# T61.net
KiCad netlist of a schematic drawn in EAGLE
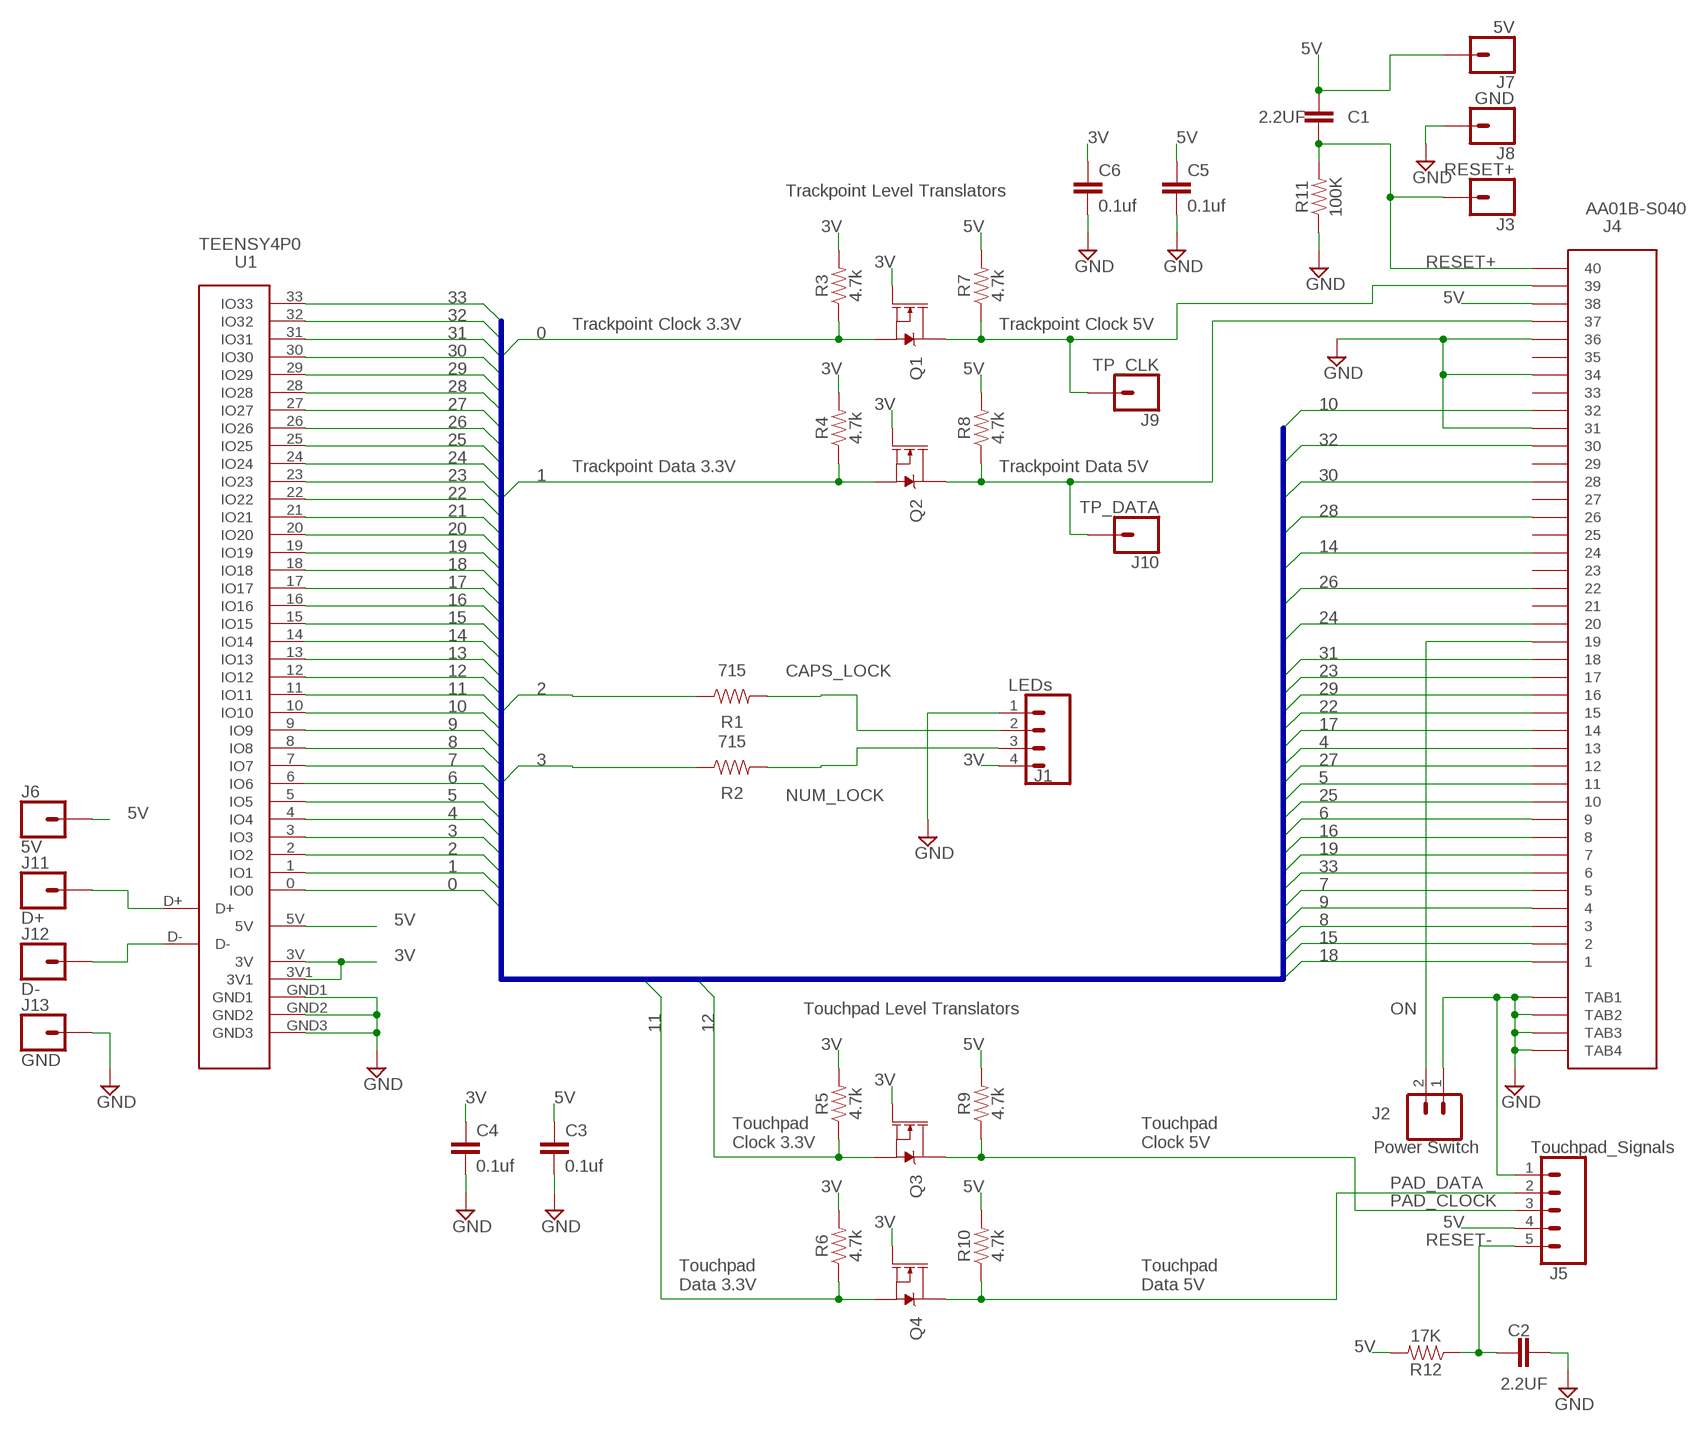
[diagram p0: schematic, sheet 1]

(export (version "E")
  (design (tool "Eeschema 10.0.6"))
  (components
    (comp (ref "C1")
      (value "2.2UF")
      (footprint "eagle-import:0603_CAP")
      (libsource (lib "eagle-import") (part "0603_CAP"))
    )
    (comp (ref "C2")
      (value "2.2UF")
      (footprint "eagle-import:0603_CAP")
      (libsource (lib "eagle-import") (part "0603_CAP"))
    )
    (comp (ref "C3")
      (value "0.1uf")
      (footprint "eagle-import:0603_CAP")
      (libsource (lib "eagle-import") (part "0603_CAP"))
    )
    (comp (ref "C4")
      (value "0.1uf")
      (footprint "eagle-import:0603_CAP")
      (libsource (lib "eagle-import") (part "0603_CAP"))
    )
    (comp (ref "C5")
      (value "0.1uf")
      (footprint "eagle-import:0603_CAP")
      (libsource (lib "eagle-import") (part "0603_CAP"))
    )
    (comp (ref "C6")
      (value "0.1uf")
      (footprint "eagle-import:0603_CAP")
      (libsource (lib "eagle-import") (part "0603_CAP"))
    )
    (comp (ref "J1")
      (value "LEDs")
      (footprint "eagle-import:1X04")
      (libsource (lib "eagle-import") (part "CONN_04"))
    )
    (comp (ref "J2")
      (value "Power Switch")
      (footprint "eagle-import:1X02")
      (libsource (lib "eagle-import") (part "CONN_02"))
    )
    (comp (ref "J3")
      (value "RESET+")
      (footprint "eagle-import:1X01_NO_SILK")
      (libsource (lib "eagle-import") (part "CONN_01PTH_NO_SILK_YES_STOP"))
    )
    (comp (ref "J4")
      (value "AA01B-S040")
      (footprint "eagle-import:WM6787_AA01B")
      (libsource (lib "eagle-import") (part "WM6787_A01B"))
    )
    (comp (ref "J5")
      (value "Touchpad_Signals")
      (footprint "eagle-import:1X05")
      (libsource (lib "eagle-import") (part "CONN_05"))
    )
    (comp (ref "J6")
      (value "5V")
      (footprint "eagle-import:1X01_NO_SILK")
      (libsource (lib "eagle-import") (part "CONN_01PTH_NO_SILK_YES_STOP"))
    )
    (comp (ref "J7")
      (value "5V")
      (footprint "eagle-import:1X01_NO_SILK")
      (libsource (lib "eagle-import") (part "CONN_01PTH_NO_SILK_YES_STOP"))
    )
    (comp (ref "J8")
      (value "GND")
      (footprint "eagle-import:1X01_NO_SILK")
      (libsource (lib "eagle-import") (part "CONN_01PTH_NO_SILK_YES_STOP"))
    )
    (comp (ref "J9")
      (value "TP_CLK")
      (footprint "eagle-import:1X01_NO_SILK")
      (libsource (lib "eagle-import") (part "CONN_01PTH_NO_SILK_YES_STOP"))
    )
    (comp (ref "J10")
      (value "TP_DATA")
      (footprint "eagle-import:1X01_NO_SILK")
      (libsource (lib "eagle-import") (part "CONN_01PTH_NO_SILK_YES_STOP"))
    )
    (comp (ref "J11")
      (value "D+")
      (footprint "eagle-import:1X01_NO_SILK")
      (libsource (lib "eagle-import") (part "CONN_01PTH_NO_SILK_YES_STOP"))
    )
    (comp (ref "J12")
      (value "D-")
      (footprint "eagle-import:1X01_NO_SILK")
      (libsource (lib "eagle-import") (part "CONN_01PTH_NO_SILK_YES_STOP"))
    )
    (comp (ref "J13")
      (value "GND")
      (footprint "eagle-import:1X01_NO_SILK")
      (libsource (lib "eagle-import") (part "CONN_01PTH_NO_SILK_YES_STOP"))
    )
    (comp (ref "Q1")
      (value "220mA/50V/3.5Ω")
      (footprint "eagle-import:SOT23-3")
      (libsource (lib "eagle-import") (part "MOSFET-NCH-BSS138"))
    )
    (comp (ref "Q2")
      (value "220mA/50V/3.5Ω")
      (footprint "eagle-import:SOT23-3")
      (libsource (lib "eagle-import") (part "MOSFET-NCH-BSS138"))
    )
    (comp (ref "Q3")
      (value "220mA/50V/3.5Ω")
      (footprint "eagle-import:SOT23-3")
      (libsource (lib "eagle-import") (part "MOSFET-NCH-BSS138"))
    )
    (comp (ref "Q4")
      (value "220mA/50V/3.5Ω")
      (footprint "eagle-import:SOT23-3")
      (libsource (lib "eagle-import") (part "MOSFET-NCH-BSS138"))
    )
    (comp (ref "R1")
      (value "715")
      (footprint "eagle-import:0603")
      (libsource (lib "eagle-import") (part "715OHM-0603-1/10W-1%"))
    )
    (comp (ref "R2")
      (value "715")
      (footprint "eagle-import:0603")
      (libsource (lib "eagle-import") (part "715OHM-0603-1/10W-1%"))
    )
    (comp (ref "R3")
      (value "4.7k")
      (footprint "eagle-import:0603")
      (libsource (lib "eagle-import") (part "4.7KOHM-0603-1/10W-1%"))
    )
    (comp (ref "R4")
      (value "4.7k")
      (footprint "eagle-import:0603")
      (libsource (lib "eagle-import") (part "4.7KOHM-0603-1/10W-1%"))
    )
    (comp (ref "R5")
      (value "4.7k")
      (footprint "eagle-import:0603")
      (libsource (lib "eagle-import") (part "4.7KOHM-0603-1/10W-1%"))
    )
    (comp (ref "R6")
      (value "4.7k")
      (footprint "eagle-import:0603")
      (libsource (lib "eagle-import") (part "4.7KOHM-0603-1/10W-1%"))
    )
    (comp (ref "R7")
      (value "4.7k")
      (footprint "eagle-import:0603")
      (libsource (lib "eagle-import") (part "4.7KOHM-0603-1/10W-1%"))
    )
    (comp (ref "R8")
      (value "4.7k")
      (footprint "eagle-import:0603")
      (libsource (lib "eagle-import") (part "4.7KOHM-0603-1/10W-1%"))
    )
    (comp (ref "R9")
      (value "4.7k")
      (footprint "eagle-import:0603")
      (libsource (lib "eagle-import") (part "4.7KOHM-0603-1/10W-1%"))
    )
    (comp (ref "R10")
      (value "4.7k")
      (footprint "eagle-import:0603")
      (libsource (lib "eagle-import") (part "4.7KOHM-0603-1/10W-1%"))
    )
    (comp (ref "R11")
      (value "100K")
      (footprint "eagle-import:0603_RESISTOR")
      (libsource (lib "eagle-import") (part "0603_RESISTOR"))
    )
    (comp (ref "R12")
      (value "17K")
      (footprint "eagle-import:0603_RESISTOR")
      (libsource (lib "eagle-import") (part "0603_RESISTOR"))
    )
    (comp (ref "U1")
      (value "TEENSY4P0")
      (footprint "eagle-import:TEENSY4P0")
      (libsource (lib "eagle-import") (part "TEENSY4P0"))
    )
  )
  (nets
    (net (code "1") (name "/0") (class "Default")
      (node (ref "Q1") (pin "2") (pinfunction "S_2") (pintype "bidirectional"))
      (node (ref "R3") (pin "1") (pinfunction "1_1") (pintype "passive"))
      (node (ref "U1") (pin "0") (pinfunction "IO0_0") (pintype "bidirectional"))
    )
    (net (code "2") (name "/1") (class "Default")
      (node (ref "Q2") (pin "2") (pinfunction "S_2") (pintype "bidirectional"))
      (node (ref "R4") (pin "1") (pinfunction "1_1") (pintype "passive"))
      (node (ref "U1") (pin "1") (pinfunction "IO1_1") (pintype "bidirectional"))
    )
    (net (code "3") (name "/2") (class "Default")
      (node (ref "R1") (pin "1") (pinfunction "1_1") (pintype "passive"))
      (node (ref "U1") (pin "2") (pinfunction "IO2_2") (pintype "bidirectional"))
    )
    (net (code "4") (name "/3") (class "Default")
      (node (ref "R2") (pin "1") (pinfunction "1_1") (pintype "passive"))
      (node (ref "U1") (pin "3") (pinfunction "IO3_3") (pintype "bidirectional"))
    )
    (net (code "5") (name "/3V") (class "Default")
      (node (ref "C4") (pin "1") (pinfunction "1_1") (pintype "passive"))
      (node (ref "C6") (pin "1") (pinfunction "1_1") (pintype "passive"))
      (node (ref "J1") (pin "4") (pinfunction "4_4") (pintype "passive"))
      (node (ref "Q1") (pin "1") (pinfunction "G_1") (pintype "bidirectional"))
      (node (ref "Q2") (pin "1") (pinfunction "G_1") (pintype "bidirectional"))
      (node (ref "Q3") (pin "1") (pinfunction "G_1") (pintype "bidirectional"))
      (node (ref "Q4") (pin "1") (pinfunction "G_1") (pintype "bidirectional"))
      (node (ref "R3") (pin "2") (pinfunction "2_2") (pintype "passive"))
      (node (ref "R4") (pin "2") (pinfunction "2_2") (pintype "passive"))
      (node (ref "R5") (pin "2") (pinfunction "2_2") (pintype "passive"))
      (node (ref "R6") (pin "2") (pinfunction "2_2") (pintype "passive"))
      (node (ref "U1") (pin "3V") (pinfunction "3V_3V") (pintype "bidirectional"))
      (node (ref "U1") (pin "3V1") (pinfunction "3V1_3V1") (pintype "bidirectional"))
    )
    (net (code "6") (name "/4") (class "Default")
      (node (ref "J4") (pin "P$13") (pinfunction "13_P$13") (pintype "bidirectional"))
      (node (ref "U1") (pin "4") (pinfunction "IO4_4") (pintype "bidirectional"))
    )
    (net (code "7") (name "/5") (class "Default")
      (node (ref "J4") (pin "P$11") (pinfunction "11_P$11") (pintype "bidirectional"))
      (node (ref "U1") (pin "5") (pinfunction "IO5_5") (pintype "bidirectional"))
    )
    (net (code "8") (name "/5V") (class "Default")
      (node (ref "C1") (pin "1") (pinfunction "1_1") (pintype "passive"))
      (node (ref "C3") (pin "1") (pinfunction "1_1") (pintype "passive"))
      (node (ref "C5") (pin "1") (pinfunction "1_1") (pintype "passive"))
      (node (ref "J4") (pin "P$38") (pinfunction "38_P$38") (pintype "bidirectional"))
      (node (ref "J5") (pin "4") (pinfunction "4_4") (pintype "passive"))
      (node (ref "J6") (pin "1") (pinfunction "1_1") (pintype "passive"))
      (node (ref "J7") (pin "1") (pinfunction "1_1") (pintype "passive"))
      (node (ref "R10") (pin "2") (pinfunction "2_2") (pintype "passive"))
      (node (ref "R12") (pin "2") (pinfunction "2_2") (pintype "passive"))
      (node (ref "R7") (pin "2") (pinfunction "2_2") (pintype "passive"))
      (node (ref "R8") (pin "2") (pinfunction "2_2") (pintype "passive"))
      (node (ref "R9") (pin "2") (pinfunction "2_2") (pintype "passive"))
      (node (ref "U1") (pin "5V") (pinfunction "5V_5V") (pintype "bidirectional"))
    )
    (net (code "9") (name "/6") (class "Default")
      (node (ref "J4") (pin "P$9") (pinfunction "9_P$9") (pintype "bidirectional"))
      (node (ref "U1") (pin "6") (pinfunction "IO6_6") (pintype "bidirectional"))
    )
    (net (code "10") (name "/7") (class "Default")
      (node (ref "J4") (pin "P$5") (pinfunction "5_P$5") (pintype "bidirectional"))
      (node (ref "U1") (pin "7") (pinfunction "IO7_7") (pintype "bidirectional"))
    )
    (net (code "11") (name "/8") (class "Default")
      (node (ref "J4") (pin "P$3") (pinfunction "3_P$3") (pintype "bidirectional"))
      (node (ref "U1") (pin "8") (pinfunction "IO8_8") (pintype "bidirectional"))
    )
    (net (code "12") (name "/9") (class "Default")
      (node (ref "J4") (pin "P$4") (pinfunction "4_P$4") (pintype "bidirectional"))
      (node (ref "U1") (pin "9") (pinfunction "IO9_9") (pintype "bidirectional"))
    )
    (net (code "13") (name "/10") (class "Default")
      (node (ref "J4") (pin "P$32") (pinfunction "32_P$32") (pintype "bidirectional"))
      (node (ref "U1") (pin "10") (pinfunction "IO10_10") (pintype "bidirectional"))
    )
    (net (code "14") (name "/11") (class "Default")
      (node (ref "Q4") (pin "2") (pinfunction "S_2") (pintype "bidirectional"))
      (node (ref "R6") (pin "1") (pinfunction "1_1") (pintype "passive"))
      (node (ref "U1") (pin "11") (pinfunction "IO11_11") (pintype "bidirectional"))
    )
    (net (code "15") (name "/12") (class "Default")
      (node (ref "Q3") (pin "2") (pinfunction "S_2") (pintype "bidirectional"))
      (node (ref "R5") (pin "1") (pinfunction "1_1") (pintype "passive"))
      (node (ref "U1") (pin "12") (pinfunction "IO12_12") (pintype "bidirectional"))
    )
    (net (code "16") (name "/13") (class "Default")
      (node (ref "U1") (pin "13") (pinfunction "IO13_13") (pintype "bidirectional"))
    )
    (net (code "17") (name "/14") (class "Default")
      (node (ref "J4") (pin "P$24") (pinfunction "24_P$24") (pintype "bidirectional"))
      (node (ref "U1") (pin "14") (pinfunction "IO14_14") (pintype "bidirectional"))
    )
    (net (code "18") (name "/15") (class "Default")
      (node (ref "J4") (pin "P$2") (pinfunction "2_P$2") (pintype "bidirectional"))
      (node (ref "U1") (pin "15") (pinfunction "IO15_15") (pintype "bidirectional"))
    )
    (net (code "19") (name "/16") (class "Default")
      (node (ref "J4") (pin "P$8") (pinfunction "8_P$8") (pintype "bidirectional"))
      (node (ref "U1") (pin "16") (pinfunction "IO16_16") (pintype "bidirectional"))
    )
    (net (code "20") (name "/17") (class "Default")
      (node (ref "J4") (pin "P$14") (pinfunction "14_P$14") (pintype "bidirectional"))
      (node (ref "U1") (pin "17") (pinfunction "IO17_17") (pintype "bidirectional"))
    )
    (net (code "21") (name "/18") (class "Default")
      (node (ref "J4") (pin "P$1") (pinfunction "1_P$1") (pintype "bidirectional"))
      (node (ref "U1") (pin "18") (pinfunction "IO18_18") (pintype "bidirectional"))
    )
    (net (code "22") (name "/19") (class "Default")
      (node (ref "J4") (pin "P$7") (pinfunction "7_P$7") (pintype "bidirectional"))
      (node (ref "U1") (pin "19") (pinfunction "IO19_19") (pintype "bidirectional"))
    )
    (net (code "23") (name "/20") (class "Default")
      (node (ref "U1") (pin "20") (pinfunction "IO20_20") (pintype "bidirectional"))
    )
    (net (code "24") (name "/21") (class "Default")
      (node (ref "U1") (pin "21") (pinfunction "IO21_21") (pintype "bidirectional"))
    )
    (net (code "25") (name "/22") (class "Default")
      (node (ref "J4") (pin "P$15") (pinfunction "15_P$15") (pintype "bidirectional"))
      (node (ref "U1") (pin "22") (pinfunction "IO22_22") (pintype "bidirectional"))
    )
    (net (code "26") (name "/23") (class "Default")
      (node (ref "J4") (pin "P$17") (pinfunction "17_P$17") (pintype "bidirectional"))
      (node (ref "U1") (pin "23") (pinfunction "IO23_23") (pintype "bidirectional"))
    )
    (net (code "27") (name "/24") (class "Default")
      (node (ref "J4") (pin "P$20") (pinfunction "20_P$20") (pintype "bidirectional"))
      (node (ref "U1") (pin "24") (pinfunction "IO24_24") (pintype "bidirectional"))
    )
    (net (code "28") (name "/25") (class "Default")
      (node (ref "J4") (pin "P$10") (pinfunction "10_P$10") (pintype "bidirectional"))
      (node (ref "U1") (pin "25") (pinfunction "IO25_25") (pintype "bidirectional"))
    )
    (net (code "29") (name "/26") (class "Default")
      (node (ref "J4") (pin "P$22") (pinfunction "22_P$22") (pintype "bidirectional"))
      (node (ref "U1") (pin "26") (pinfunction "IO26_26") (pintype "bidirectional"))
    )
    (net (code "30") (name "/27") (class "Default")
      (node (ref "J4") (pin "P$12") (pinfunction "12_P$12") (pintype "bidirectional"))
      (node (ref "U1") (pin "27") (pinfunction "IO27_27") (pintype "bidirectional"))
    )
    (net (code "31") (name "/28") (class "Default")
      (node (ref "J4") (pin "P$26") (pinfunction "26_P$26") (pintype "bidirectional"))
      (node (ref "U1") (pin "28") (pinfunction "IO28_28") (pintype "bidirectional"))
    )
    (net (code "32") (name "/29") (class "Default")
      (node (ref "J4") (pin "P$16") (pinfunction "16_P$16") (pintype "bidirectional"))
      (node (ref "U1") (pin "29") (pinfunction "IO29_29") (pintype "bidirectional"))
    )
    (net (code "33") (name "/30") (class "Default")
      (node (ref "J4") (pin "P$28") (pinfunction "28_P$28") (pintype "bidirectional"))
      (node (ref "U1") (pin "30") (pinfunction "IO30_30") (pintype "bidirectional"))
    )
    (net (code "34") (name "/31") (class "Default")
      (node (ref "J4") (pin "P$18") (pinfunction "18_P$18") (pintype "bidirectional"))
      (node (ref "U1") (pin "31") (pinfunction "IO31_31") (pintype "bidirectional"))
    )
    (net (code "35") (name "/32") (class "Default")
      (node (ref "J4") (pin "P$30") (pinfunction "30_P$30") (pintype "bidirectional"))
      (node (ref "U1") (pin "32") (pinfunction "IO32_32") (pintype "bidirectional"))
    )
    (net (code "36") (name "/33") (class "Default")
      (node (ref "J4") (pin "P$6") (pinfunction "6_P$6") (pintype "bidirectional"))
      (node (ref "U1") (pin "33") (pinfunction "IO33_33") (pintype "bidirectional"))
    )
    (net (code "37") (name "/CAPS_LOCK") (class "Default")
      (node (ref "J1") (pin "2") (pinfunction "2_2") (pintype "passive"))
      (node (ref "R1") (pin "2") (pinfunction "2_2") (pintype "passive"))
    )
    (net (code "38") (name "/NUM_LOCK") (class "Default")
      (node (ref "J1") (pin "3") (pinfunction "3_3") (pintype "passive"))
      (node (ref "R2") (pin "2") (pinfunction "2_2") (pintype "passive"))
    )
    (net (code "39") (name "/ON") (class "Default")
      (node (ref "J2") (pin "2") (pinfunction "2_2") (pintype "passive"))
      (node (ref "J4") (pin "P$19") (pinfunction "19_P$19") (pintype "bidirectional"))
    )
    (net (code "40") (name "/PAD_CLOCK") (class "Default")
      (node (ref "J5") (pin "3") (pinfunction "3_3") (pintype "passive"))
      (node (ref "Q3") (pin "3") (pinfunction "D_3") (pintype "bidirectional"))
      (node (ref "R9") (pin "1") (pinfunction "1_1") (pintype "passive"))
    )
    (net (code "41") (name "/PAD_DATA") (class "Default")
      (node (ref "J5") (pin "2") (pinfunction "2_2") (pintype "passive"))
      (node (ref "Q4") (pin "3") (pinfunction "D_3") (pintype "bidirectional"))
      (node (ref "R10") (pin "1") (pinfunction "1_1") (pintype "passive"))
    )
    (net (code "42") (name "/RESET+") (class "Default")
      (node (ref "C1") (pin "2") (pinfunction "2_2") (pintype "passive"))
      (node (ref "J3") (pin "1") (pinfunction "1_1") (pintype "passive"))
      (node (ref "J4") (pin "P$40") (pinfunction "40_P$40") (pintype "bidirectional"))
      (node (ref "R11") (pin "2") (pinfunction "2_2") (pintype "passive"))
    )
    (net (code "43") (name "/RESET-") (class "Default")
      (node (ref "C2") (pin "1") (pinfunction "1_1") (pintype "passive"))
      (node (ref "J5") (pin "5") (pinfunction "5_5") (pintype "passive"))
      (node (ref "R12") (pin "1") (pinfunction "1_1") (pintype "passive"))
    )
    (net (code "44") (name "GND") (class "Default")
      (node (ref "C2") (pin "2") (pinfunction "2_2") (pintype "passive"))
      (node (ref "C3") (pin "2") (pinfunction "2_2") (pintype "passive"))
      (node (ref "C4") (pin "2") (pinfunction "2_2") (pintype "passive"))
      (node (ref "C5") (pin "2") (pinfunction "2_2") (pintype "passive"))
      (node (ref "C6") (pin "2") (pinfunction "2_2") (pintype "passive"))
      (node (ref "J1") (pin "1") (pinfunction "1_1") (pintype "passive"))
      (node (ref "J13") (pin "1") (pinfunction "1_1") (pintype "passive"))
      (node (ref "J2") (pin "1") (pinfunction "1_1") (pintype "passive"))
      (node (ref "J4") (pin "P$31") (pinfunction "31_P$31") (pintype "bidirectional"))
      (node (ref "J4") (pin "P$34") (pinfunction "34_P$34") (pintype "bidirectional"))
      (node (ref "J4") (pin "P$36") (pinfunction "36_P$36") (pintype "bidirectional"))
      (node (ref "J4") (pin "TAB1") (pinfunction "TAB1_TAB1") (pintype "bidirectional"))
      (node (ref "J4") (pin "TAB2") (pinfunction "TAB2_TAB2") (pintype "bidirectional"))
      (node (ref "J4") (pin "TAB3") (pinfunction "TAB3_TAB3") (pintype "bidirectional"))
      (node (ref "J4") (pin "TAB4") (pinfunction "TAB4_TAB4") (pintype "bidirectional"))
      (node (ref "J5") (pin "1") (pinfunction "1_1") (pintype "passive"))
      (node (ref "J8") (pin "1") (pinfunction "1_1") (pintype "passive"))
      (node (ref "R11") (pin "1") (pinfunction "1_1") (pintype "passive"))
      (node (ref "U1") (pin "GND1") (pinfunction "GND1_GND1") (pintype "bidirectional"))
      (node (ref "U1") (pin "GND2") (pinfunction "GND2_GND2") (pintype "bidirectional"))
      (node (ref "U1") (pin "GND3") (pinfunction "GND3_GND3") (pintype "bidirectional"))
    )
    (net (code "45") (name "Net-(J4-37)") (class "Default")
      (node (ref "J10") (pin "1") (pinfunction "1_1") (pintype "passive"))
      (node (ref "J4") (pin "P$37") (pinfunction "37_P$37") (pintype "bidirectional"))
      (node (ref "Q2") (pin "3") (pinfunction "D_3") (pintype "bidirectional"))
      (node (ref "R8") (pin "1") (pinfunction "1_1") (pintype "passive"))
    )
    (net (code "46") (name "Net-(J4-39)") (class "Default")
      (node (ref "J4") (pin "P$39") (pinfunction "39_P$39") (pintype "bidirectional"))
      (node (ref "J9") (pin "1") (pinfunction "1_1") (pintype "passive"))
      (node (ref "Q1") (pin "3") (pinfunction "D_3") (pintype "bidirectional"))
      (node (ref "R7") (pin "1") (pinfunction "1_1") (pintype "passive"))
    )
    (net (code "47") (name "Net-(J11-Pad1)") (class "Default")
      (node (ref "J11") (pin "1") (pinfunction "1_1") (pintype "passive"))
      (node (ref "U1") (pin "D+") (pinfunction "D+_D+") (pintype "bidirectional"))
    )
    (net (code "48") (name "Net-(J12-Pad1)") (class "Default")
      (node (ref "J12") (pin "1") (pinfunction "1_1") (pintype "passive"))
      (node (ref "U1") (pin "D-") (pinfunction "D-_D-") (pintype "bidirectional"))
    )
    (net (code "49") (name "unconnected-(J4-21-PadP$21)") (class "Default")
      (node (ref "J4") (pin "P$21") (pinfunction "21_P$21") (pintype "bidirectional"))
    )
    (net (code "50") (name "unconnected-(J4-23-PadP$23)") (class "Default")
      (node (ref "J4") (pin "P$23") (pinfunction "23_P$23") (pintype "bidirectional"))
    )
    (net (code "51") (name "unconnected-(J4-25-PadP$25)") (class "Default")
      (node (ref "J4") (pin "P$25") (pinfunction "25_P$25") (pintype "bidirectional"))
    )
    (net (code "52") (name "unconnected-(J4-27-PadP$27)") (class "Default")
      (node (ref "J4") (pin "P$27") (pinfunction "27_P$27") (pintype "bidirectional"))
    )
    (net (code "53") (name "unconnected-(J4-29-PadP$29)") (class "Default")
      (node (ref "J4") (pin "P$29") (pinfunction "29_P$29") (pintype "bidirectional"))
    )
    (net (code "54") (name "unconnected-(J4-33-PadP$33)") (class "Default")
      (node (ref "J4") (pin "P$33") (pinfunction "33_P$33") (pintype "bidirectional"))
    )
    (net (code "55") (name "unconnected-(J4-35-PadP$35)") (class "Default")
      (node (ref "J4") (pin "P$35") (pinfunction "35_P$35") (pintype "bidirectional"))
    )
  )
)
